# KeeponNewVersion.net
KiCad netlist of a schematic drawn in EAGLE
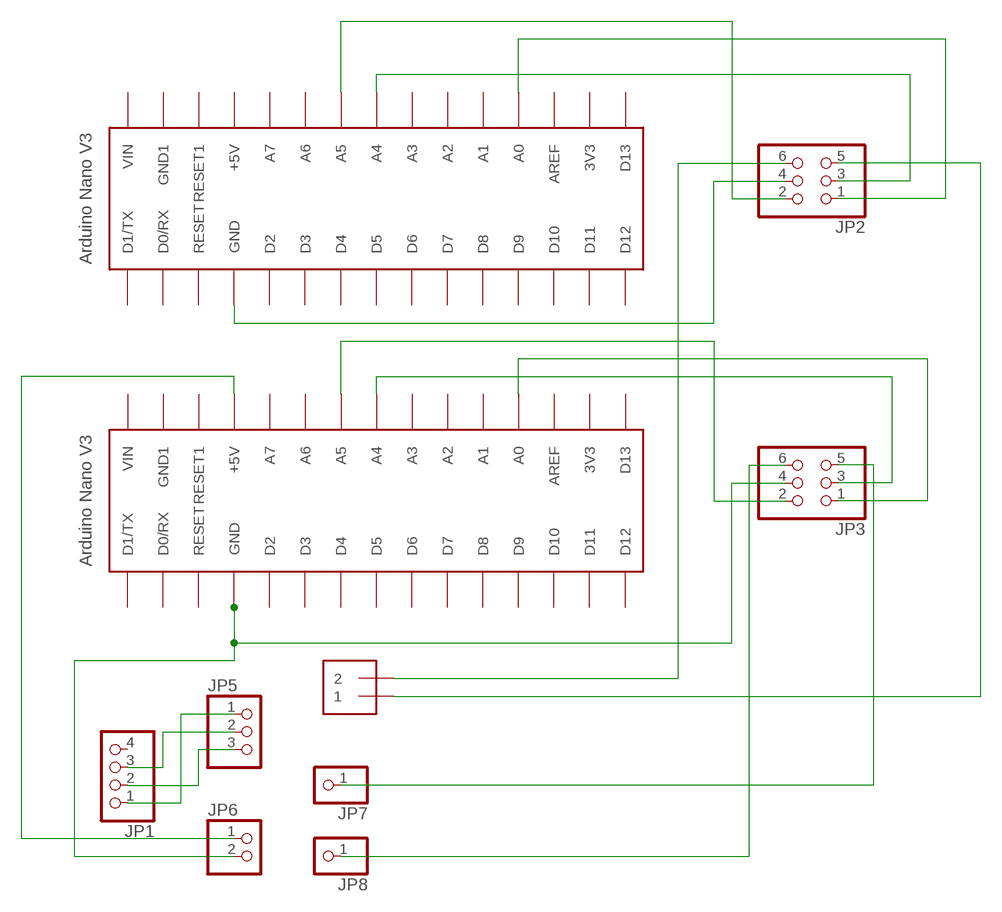
[diagram p0: schematic, sheet 1]

(export (version "E")
  (design (tool "Eeschema 10.0.6"))
  (components
    (comp (ref "J1")
      (value "1X2-3.5MM")
      (footprint "eagle-import:1X2-3.5MM")
      (libsource (lib "eagle-import") (part "1X2-3.5MM"))
    )
    (comp (ref "JP1")
      (value "PINHD-1X4")
      (footprint "eagle-import:1X04")
      (libsource (lib "eagle-import") (part "PINHD-1X4"))
    )
    (comp (ref "JP2")
      (value "PINHD-2X3")
      (footprint "eagle-import:2X03")
      (libsource (lib "eagle-import") (part "PINHD-2X3"))
    )
    (comp (ref "JP3")
      (value "PINHD-2X3")
      (footprint "eagle-import:2X03")
      (libsource (lib "eagle-import") (part "PINHD-2X3"))
    )
    (comp (ref "JP5")
      (value "PINHD-1X3")
      (footprint "eagle-import:1X03")
      (libsource (lib "eagle-import") (part "PINHD-1X3"))
    )
    (comp (ref "JP6")
      (value "PINHD-1X2")
      (footprint "eagle-import:1X02")
      (libsource (lib "eagle-import") (part "PINHD-1X2"))
    )
    (comp (ref "JP7")
      (value "PINHD-1X1")
      (footprint "eagle-import:1X01")
      (libsource (lib "eagle-import") (part "PINHD-1X1"))
    )
    (comp (ref "JP8")
      (value "PINHD-1X1")
      (footprint "eagle-import:1X01")
      (libsource (lib "eagle-import") (part "PINHD-1X1"))
    )
    (comp (ref "U$2")
      (value "ARDUINONANO")
      (footprint "eagle-import:PDIP-32")
      (libsource (lib "eagle-import") (part "ARDUINONANO"))
    )
    (comp (ref "U$3")
      (value "ARDUINONANO")
      (footprint "eagle-import:PDIP-32")
      (libsource (lib "eagle-import") (part "ARDUINONANO"))
    )
  )
  (nets
    (net (code "1") (name "/GND") (class "Default")
      (node (ref "JP2") (pin "4") (pinfunction "4_4") (pintype "passive"))
      (node (ref "JP3") (pin "4") (pinfunction "4_4") (pintype "passive"))
      (node (ref "JP6") (pin "2") (pinfunction "2_2") (pintype "passive"))
      (node (ref "U$2") (pin "GND") (pinfunction "GND_GND") (pintype "bidirectional"))
      (node (ref "U$3") (pin "GND") (pinfunction "GND_GND") (pintype "bidirectional"))
    )
    (net (code "2") (name "Net-(J1-Pad1)") (class "Default")
      (node (ref "J1") (pin "1") (pinfunction "1_1") (pintype "passive"))
      (node (ref "JP2") (pin "5") (pinfunction "5_5") (pintype "passive"))
    )
    (net (code "3") (name "Net-(J1-Pad2)") (class "Default")
      (node (ref "J1") (pin "2") (pinfunction "2_2") (pintype "passive"))
      (node (ref "JP2") (pin "6") (pinfunction "6_6") (pintype "passive"))
    )
    (net (code "4") (name "Net-(JP1-Pad1)") (class "Default")
      (node (ref "JP1") (pin "1") (pinfunction "1_1") (pintype "passive"))
      (node (ref "JP5") (pin "1") (pinfunction "1_1") (pintype "passive"))
    )
    (net (code "5") (name "Net-(JP1-Pad2)") (class "Default")
      (node (ref "JP1") (pin "2") (pinfunction "2_2") (pintype "passive"))
      (node (ref "JP5") (pin "3") (pinfunction "3_3") (pintype "passive"))
    )
    (net (code "6") (name "Net-(JP1-Pad3)") (class "Default")
      (node (ref "JP1") (pin "3") (pinfunction "3_3") (pintype "passive"))
      (node (ref "JP5") (pin "2") (pinfunction "2_2") (pintype "passive"))
    )
    (net (code "7") (name "Net-(JP3-Pad5)") (class "Default")
      (node (ref "JP3") (pin "5") (pinfunction "5_5") (pintype "passive"))
      (node (ref "JP7") (pin "1") (pinfunction "1_1") (pintype "passive"))
    )
    (net (code "8") (name "Net-(JP3-Pad6)") (class "Default")
      (node (ref "JP3") (pin "6") (pinfunction "6_6") (pintype "passive"))
      (node (ref "JP8") (pin "1") (pinfunction "1_1") (pintype "passive"))
    )
    (net (code "9") (name "Net-(JP6-Pad1)") (class "Default")
      (node (ref "JP6") (pin "1") (pinfunction "1_1") (pintype "passive"))
      (node (ref "U$2") (pin "+5V") (pinfunction "+5V_+5V") (pintype "bidirectional"))
    )
    (net (code "10") (name "Net-(U$2-A0)") (class "Default")
      (node (ref "JP3") (pin "1") (pinfunction "1_1") (pintype "passive"))
      (node (ref "U$2") (pin "A7") (pinfunction "A0_A7") (pintype "bidirectional"))
    )
    (net (code "11") (name "Net-(U$2-A4)") (class "Default")
      (node (ref "JP3") (pin "3") (pinfunction "3_3") (pintype "passive"))
      (node (ref "U$2") (pin "A3") (pinfunction "A4_A3") (pintype "bidirectional"))
    )
    (net (code "12") (name "Net-(U$2-A5)") (class "Default")
      (node (ref "JP3") (pin "2") (pinfunction "2_2") (pintype "passive"))
      (node (ref "U$2") (pin "A2") (pinfunction "A5_A2") (pintype "bidirectional"))
    )
    (net (code "13") (name "Net-(U$3-A0)") (class "Default")
      (node (ref "JP2") (pin "1") (pinfunction "1_1") (pintype "passive"))
      (node (ref "U$3") (pin "A7") (pinfunction "A0_A7") (pintype "bidirectional"))
    )
    (net (code "14") (name "Net-(U$3-A4)") (class "Default")
      (node (ref "JP2") (pin "3") (pinfunction "3_3") (pintype "passive"))
      (node (ref "U$3") (pin "A3") (pinfunction "A4_A3") (pintype "bidirectional"))
    )
    (net (code "15") (name "Net-(U$3-A5)") (class "Default")
      (node (ref "JP2") (pin "2") (pinfunction "2_2") (pintype "passive"))
      (node (ref "U$3") (pin "A2") (pinfunction "A5_A2") (pintype "bidirectional"))
    )
    (net (code "16") (name "unconnected-(JP1-Pad4)") (class "Default")
      (node (ref "JP1") (pin "4") (pinfunction "4_4") (pintype "passive"))
    )
    (net (code "17") (name "unconnected-(U$2-A1-PadA6)") (class "Default")
      (node (ref "U$2") (pin "A6") (pinfunction "A1_A6") (pintype "bidirectional"))
    )
    (net (code "18") (name "unconnected-(U$2-A2-PadA5)") (class "Default")
      (node (ref "U$2") (pin "A5") (pinfunction "A2_A5") (pintype "bidirectional"))
    )
    (net (code "19") (name "unconnected-(U$2-A3-PadA4)") (class "Default")
      (node (ref "U$2") (pin "A4") (pinfunction "A3_A4") (pintype "bidirectional"))
    )
    (net (code "20") (name "unconnected-(U$2-A6-PadA1)") (class "Default")
      (node (ref "U$2") (pin "A1") (pinfunction "A6_A1") (pintype "bidirectional"))
    )
    (net (code "21") (name "unconnected-(U$2-A7-PadA0)") (class "Default")
      (node (ref "U$2") (pin "A0") (pinfunction "A7_A0") (pintype "bidirectional"))
    )
    (net (code "22") (name "unconnected-(U$2-Pad3V3)") (class "Default")
      (node (ref "U$2") (pin "3V3") (pinfunction "3V3_3V3") (pintype "bidirectional"))
    )
    (net (code "23") (name "unconnected-(U$2-PadAREF)") (class "Default")
      (node (ref "U$2") (pin "AREF") (pinfunction "AREF_AREF") (pintype "bidirectional"))
    )
    (net (code "24") (name "unconnected-(U$2-PadD0{slash}RX)") (class "Default")
      (node (ref "U$2") (pin "D0/RX") (pinfunction "D0/RX_D0/RX") (pintype "bidirectional"))
    )
    (net (code "25") (name "unconnected-(U$2-PadD1{slash}TX)") (class "Default")
      (node (ref "U$2") (pin "D1/TX") (pinfunction "D1/TX_D1/TX") (pintype "bidirectional"))
    )
    (net (code "26") (name "unconnected-(U$2-PadD2)") (class "Default")
      (node (ref "U$2") (pin "D2") (pinfunction "D2_D2") (pintype "bidirectional"))
    )
    (net (code "27") (name "unconnected-(U$2-PadD3)") (class "Default")
      (node (ref "U$2") (pin "D3") (pinfunction "D3_D3") (pintype "bidirectional"))
    )
    (net (code "28") (name "unconnected-(U$2-PadD4)") (class "Default")
      (node (ref "U$2") (pin "D4") (pinfunction "D4_D4") (pintype "bidirectional"))
    )
    (net (code "29") (name "unconnected-(U$2-PadD5)") (class "Default")
      (node (ref "U$2") (pin "D5") (pinfunction "D5_D5") (pintype "bidirectional"))
    )
    (net (code "30") (name "unconnected-(U$2-PadD6)") (class "Default")
      (node (ref "U$2") (pin "D6") (pinfunction "D6_D6") (pintype "bidirectional"))
    )
    (net (code "31") (name "unconnected-(U$2-PadD7)") (class "Default")
      (node (ref "U$2") (pin "D7") (pinfunction "D7_D7") (pintype "bidirectional"))
    )
    (net (code "32") (name "unconnected-(U$2-PadD8)") (class "Default")
      (node (ref "U$2") (pin "D8") (pinfunction "D8_D8") (pintype "bidirectional"))
    )
    (net (code "33") (name "unconnected-(U$2-PadD9)") (class "Default")
      (node (ref "U$2") (pin "D9") (pinfunction "D9_D9") (pintype "bidirectional"))
    )
    (net (code "34") (name "unconnected-(U$2-PadD10)") (class "Default")
      (node (ref "U$2") (pin "D10") (pinfunction "D10_D10") (pintype "bidirectional"))
    )
    (net (code "35") (name "unconnected-(U$2-PadD11)") (class "Default")
      (node (ref "U$2") (pin "D11") (pinfunction "D11_D11") (pintype "bidirectional"))
    )
    (net (code "36") (name "unconnected-(U$2-PadD12)") (class "Default")
      (node (ref "U$2") (pin "D12") (pinfunction "D12_D12") (pintype "bidirectional"))
    )
    (net (code "37") (name "unconnected-(U$2-PadD13)") (class "Default")
      (node (ref "U$2") (pin "D13") (pinfunction "D13_D13") (pintype "bidirectional"))
    )
    (net (code "38") (name "unconnected-(U$2-PadGND1)") (class "Default")
      (node (ref "U$2") (pin "GND1") (pinfunction "GND1_GND1") (pintype "bidirectional"))
    )
    (net (code "39") (name "unconnected-(U$2-PadRESET)") (class "Default")
      (node (ref "U$2") (pin "RESET") (pinfunction "RESET_RESET") (pintype "bidirectional"))
    )
    (net (code "40") (name "unconnected-(U$2-PadRESET1)") (class "Default")
      (node (ref "U$2") (pin "RESET1") (pinfunction "RESET1_RESET1") (pintype "bidirectional"))
    )
    (net (code "41") (name "unconnected-(U$2-PadVIN)") (class "Default")
      (node (ref "U$2") (pin "VIN") (pinfunction "VIN_VIN") (pintype "bidirectional"))
    )
    (net (code "42") (name "unconnected-(U$3-A1-PadA6)") (class "Default")
      (node (ref "U$3") (pin "A6") (pinfunction "A1_A6") (pintype "bidirectional"))
    )
    (net (code "43") (name "unconnected-(U$3-A2-PadA5)") (class "Default")
      (node (ref "U$3") (pin "A5") (pinfunction "A2_A5") (pintype "bidirectional"))
    )
    (net (code "44") (name "unconnected-(U$3-A3-PadA4)") (class "Default")
      (node (ref "U$3") (pin "A4") (pinfunction "A3_A4") (pintype "bidirectional"))
    )
    (net (code "45") (name "unconnected-(U$3-A6-PadA1)") (class "Default")
      (node (ref "U$3") (pin "A1") (pinfunction "A6_A1") (pintype "bidirectional"))
    )
    (net (code "46") (name "unconnected-(U$3-A7-PadA0)") (class "Default")
      (node (ref "U$3") (pin "A0") (pinfunction "A7_A0") (pintype "bidirectional"))
    )
    (net (code "47") (name "unconnected-(U$3-Pad+5V)") (class "Default")
      (node (ref "U$3") (pin "+5V") (pinfunction "+5V_+5V") (pintype "bidirectional"))
    )
    (net (code "48") (name "unconnected-(U$3-Pad3V3)") (class "Default")
      (node (ref "U$3") (pin "3V3") (pinfunction "3V3_3V3") (pintype "bidirectional"))
    )
    (net (code "49") (name "unconnected-(U$3-PadAREF)") (class "Default")
      (node (ref "U$3") (pin "AREF") (pinfunction "AREF_AREF") (pintype "bidirectional"))
    )
    (net (code "50") (name "unconnected-(U$3-PadD0{slash}RX)") (class "Default")
      (node (ref "U$3") (pin "D0/RX") (pinfunction "D0/RX_D0/RX") (pintype "bidirectional"))
    )
    (net (code "51") (name "unconnected-(U$3-PadD1{slash}TX)") (class "Default")
      (node (ref "U$3") (pin "D1/TX") (pinfunction "D1/TX_D1/TX") (pintype "bidirectional"))
    )
    (net (code "52") (name "unconnected-(U$3-PadD2)") (class "Default")
      (node (ref "U$3") (pin "D2") (pinfunction "D2_D2") (pintype "bidirectional"))
    )
    (net (code "53") (name "unconnected-(U$3-PadD3)") (class "Default")
      (node (ref "U$3") (pin "D3") (pinfunction "D3_D3") (pintype "bidirectional"))
    )
    (net (code "54") (name "unconnected-(U$3-PadD4)") (class "Default")
      (node (ref "U$3") (pin "D4") (pinfunction "D4_D4") (pintype "bidirectional"))
    )
    (net (code "55") (name "unconnected-(U$3-PadD5)") (class "Default")
      (node (ref "U$3") (pin "D5") (pinfunction "D5_D5") (pintype "bidirectional"))
    )
    (net (code "56") (name "unconnected-(U$3-PadD6)") (class "Default")
      (node (ref "U$3") (pin "D6") (pinfunction "D6_D6") (pintype "bidirectional"))
    )
    (net (code "57") (name "unconnected-(U$3-PadD7)") (class "Default")
      (node (ref "U$3") (pin "D7") (pinfunction "D7_D7") (pintype "bidirectional"))
    )
    (net (code "58") (name "unconnected-(U$3-PadD8)") (class "Default")
      (node (ref "U$3") (pin "D8") (pinfunction "D8_D8") (pintype "bidirectional"))
    )
    (net (code "59") (name "unconnected-(U$3-PadD9)") (class "Default")
      (node (ref "U$3") (pin "D9") (pinfunction "D9_D9") (pintype "bidirectional"))
    )
    (net (code "60") (name "unconnected-(U$3-PadD10)") (class "Default")
      (node (ref "U$3") (pin "D10") (pinfunction "D10_D10") (pintype "bidirectional"))
    )
    (net (code "61") (name "unconnected-(U$3-PadD11)") (class "Default")
      (node (ref "U$3") (pin "D11") (pinfunction "D11_D11") (pintype "bidirectional"))
    )
    (net (code "62") (name "unconnected-(U$3-PadD12)") (class "Default")
      (node (ref "U$3") (pin "D12") (pinfunction "D12_D12") (pintype "bidirectional"))
    )
    (net (code "63") (name "unconnected-(U$3-PadD13)") (class "Default")
      (node (ref "U$3") (pin "D13") (pinfunction "D13_D13") (pintype "bidirectional"))
    )
    (net (code "64") (name "unconnected-(U$3-PadGND1)") (class "Default")
      (node (ref "U$3") (pin "GND1") (pinfunction "GND1_GND1") (pintype "bidirectional"))
    )
    (net (code "65") (name "unconnected-(U$3-PadRESET)") (class "Default")
      (node (ref "U$3") (pin "RESET") (pinfunction "RESET_RESET") (pintype "bidirectional"))
    )
    (net (code "66") (name "unconnected-(U$3-PadRESET1)") (class "Default")
      (node (ref "U$3") (pin "RESET1") (pinfunction "RESET1_RESET1") (pintype "bidirectional"))
    )
    (net (code "67") (name "unconnected-(U$3-PadVIN)") (class "Default")
      (node (ref "U$3") (pin "VIN") (pinfunction "VIN_VIN") (pintype "bidirectional"))
    )
  )
)
